# SNES_TST_Sheet3.net
KiCad netlist of a schematic drawn in Altium Designer
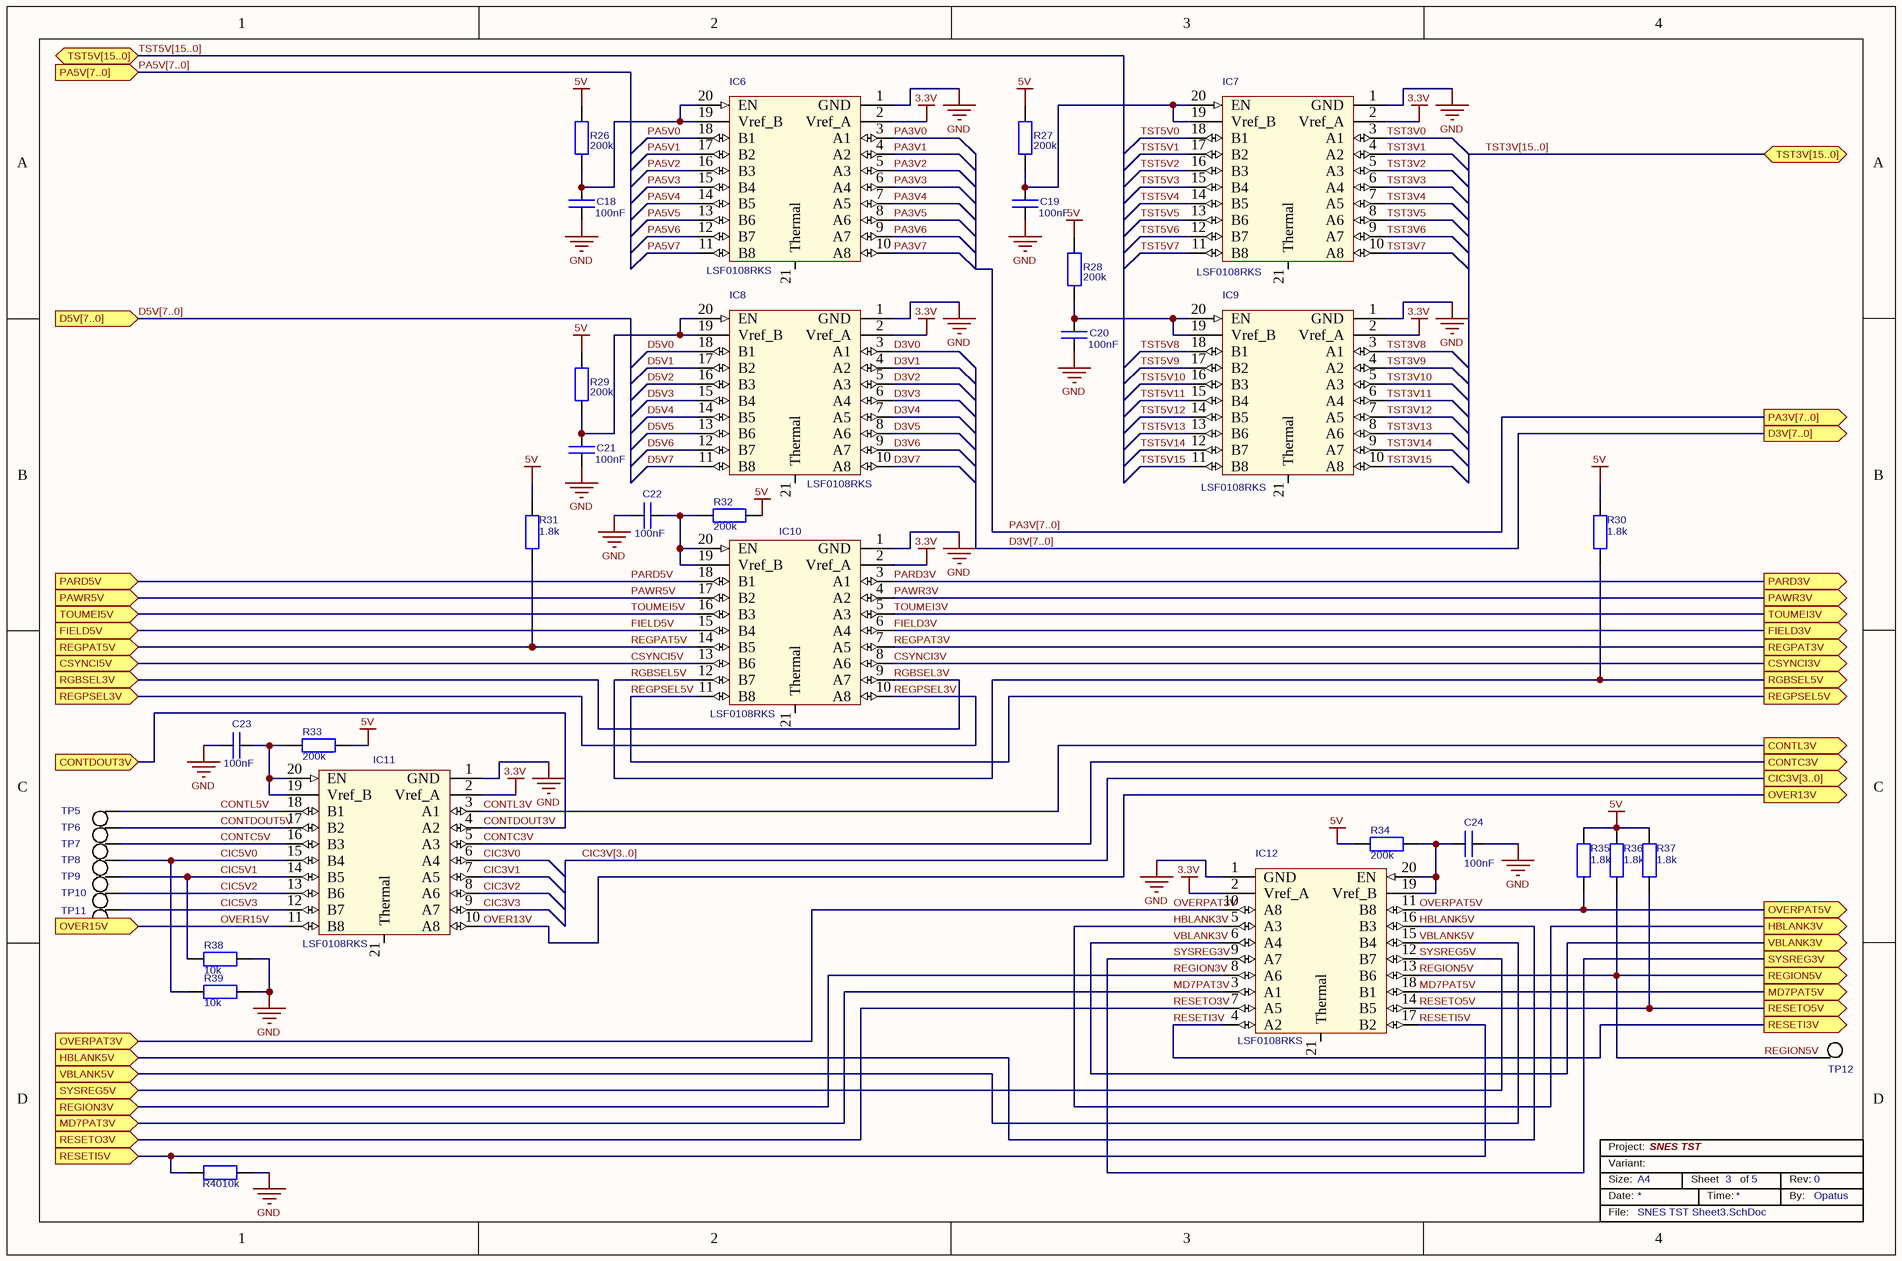
[diagram p0: SNES TST Sheet3.SchDoc]

(export (version "E")
  (design (tool "Eeschema 10.0.6"))
  (components
    (comp (ref "C18")
      (value "100nF")
      (footprint "Cap_0402_Chip")
      (fields
        (field (name "TOLERANCE") "±20%")
        (field (name "Comment") "Ceramic Capacitor 100nF 10V ±20% X7R 0402")
      )
      (libsource (lib "PCB") (part "Capacitor"))
    )
    (comp (ref "C19")
      (value "100nF")
      (footprint "Cap_0402_Chip")
      (fields
        (field (name "TOLERANCE") "±20%")
        (field (name "Comment") "Ceramic Capacitor 100nF 10V ±20% X7R 0402")
      )
      (libsource (lib "PCB") (part "Capacitor"))
    )
    (comp (ref "C20")
      (value "100nF")
      (footprint "Cap_0402_Chip")
      (fields
        (field (name "TOLERANCE") "±20%")
        (field (name "Comment") "Ceramic Capacitor 100nF 10V ±20% X7R 0402")
      )
      (libsource (lib "PCB") (part "Capacitor"))
    )
    (comp (ref "C21")
      (value "100nF")
      (footprint "Cap_0402_Chip")
      (fields
        (field (name "TOLERANCE") "±20%")
        (field (name "Comment") "Ceramic Capacitor 100nF 10V ±20% X7R 0402")
      )
      (libsource (lib "PCB") (part "Capacitor"))
    )
    (comp (ref "C22")
      (value "100nF")
      (footprint "Cap_0402_Chip")
      (fields
        (field (name "TOLERANCE") "±20%")
        (field (name "Comment") "Ceramic Capacitor 100nF 10V ±20% X7R 0402")
      )
      (libsource (lib "PCB") (part "Capacitor"))
    )
    (comp (ref "C23")
      (value "100nF")
      (footprint "Cap_0402_Chip")
      (fields
        (field (name "TOLERANCE") "±20%")
        (field (name "Comment") "Ceramic Capacitor 100nF 10V ±20% X7R 0402")
      )
      (libsource (lib "PCB") (part "Capacitor"))
    )
    (comp (ref "C24")
      (value "100nF")
      (footprint "Cap_0402_Chip")
      (fields
        (field (name "TOLERANCE") "±20%")
        (field (name "Comment") "Ceramic Capacitor 100nF 10V ±20% X7R 0402")
      )
      (libsource (lib "PCB") (part "Capacitor"))
    )
    (comp (ref "IC6")
      (value "LSF0108")
      (footprint "VQFN20")
      (description "8-bit level shifter")
      (fields (field (name "MANUFACTURER_PART_NUMBER") "LSF0108RKS"))
      (libsource (lib "PCB") (part "LSF0108DCUR"))
    )
    (comp (ref "IC7")
      (value "LSF0108")
      (footprint "VQFN20")
      (description "8-bit level shifter")
      (fields (field (name "MANUFACTURER_PART_NUMBER") "LSF0108RKS"))
      (libsource (lib "PCB") (part "LSF0108DCUR"))
    )
    (comp (ref "IC8")
      (value "LSF0108")
      (footprint "VQFN20")
      (description "8-bit level shifter")
      (fields (field (name "MANUFACTURER_PART_NUMBER") "LSF0108RKS"))
      (libsource (lib "PCB") (part "LSF0108DCUR"))
    )
    (comp (ref "IC9")
      (value "LSF0108")
      (footprint "VQFN20")
      (description "8-bit level shifter")
      (fields (field (name "MANUFACTURER_PART_NUMBER") "LSF0108RKS"))
      (libsource (lib "PCB") (part "LSF0108DCUR"))
    )
    (comp (ref "IC10")
      (value "LSF0108")
      (footprint "VQFN20")
      (description "8-bit level shifter")
      (fields (field (name "MANUFACTURER_PART_NUMBER") "LSF0108RKS"))
      (libsource (lib "PCB") (part "LSF0108DCUR"))
    )
    (comp (ref "IC11")
      (value "LSF0108")
      (footprint "VQFN20")
      (description "8-bit level shifter")
      (fields (field (name "MANUFACTURER_PART_NUMBER") "LSF0108RKS"))
      (libsource (lib "PCB") (part "LSF0108DCUR"))
    )
    (comp (ref "IC12")
      (value "LSF0108")
      (footprint "VQFN20")
      (description "8-bit level shifter")
      (fields (field (name "MANUFACTURER_PART_NUMBER") "LSF0108RKS"))
      (libsource (lib "") (part "LSF0108DCUR_1"))
    )
    (comp (ref "R26")
      (value "200k")
      (footprint "Res_0402_Chip")
      (fields (field (name "TOLERANCE") "±1%") (field (name "Comment") "Resistor 200k 0402 ±1%"))
      (libsource (lib "") (part "R_2"))
    )
    (comp (ref "R27")
      (value "200k")
      (footprint "Res_0402_Chip")
      (fields (field (name "TOLERANCE") "±1%") (field (name "Comment") "Resistor 200k 0402 ±1%"))
      (libsource (lib "") (part "R_2"))
    )
    (comp (ref "R28")
      (value "200k")
      (footprint "Res_0402_Chip")
      (fields (field (name "TOLERANCE") "±1%") (field (name "Comment") "Resistor 200k 0402 ±1%"))
      (libsource (lib "") (part "R_2"))
    )
    (comp (ref "R29")
      (value "200k")
      (footprint "Res_0402_Chip")
      (fields (field (name "TOLERANCE") "±1%") (field (name "Comment") "Resistor 200k 0402 ±1%"))
      (libsource (lib "") (part "R_2"))
    )
    (comp (ref "R30")
      (value "1.8k")
      (footprint "Res_0402_Chip")
      (fields (field (name "TOLERANCE") "±1%") (field (name "Comment") "Resistor 1.8k 0402 ±1%"))
      (libsource (lib "PCB") (part "R"))
    )
    (comp (ref "R31")
      (value "1.8k")
      (footprint "Res_0402_Chip")
      (fields (field (name "TOLERANCE") "±1%") (field (name "Comment") "Resistor 1.8k 0402 ±1%"))
      (libsource (lib "PCB") (part "R"))
    )
    (comp (ref "R32")
      (value "200k")
      (footprint "Res_0402_Chip")
      (fields (field (name "TOLERANCE") "±1%") (field (name "Comment") "Resistor 200k 0402 ±1%"))
      (libsource (lib "") (part "R_1"))
    )
    (comp (ref "R33")
      (value "200k")
      (footprint "Res_0402_Chip")
      (fields (field (name "TOLERANCE") "±1%") (field (name "Comment") "Resistor 200k 0402 ±1%"))
      (libsource (lib "") (part "R_1"))
    )
    (comp (ref "R34")
      (value "200k")
      (footprint "Res_0402_Chip")
      (fields (field (name "TOLERANCE") "±1%") (field (name "Comment") "Resistor 200k 0402 ±1%"))
      (libsource (lib "") (part "R_1"))
    )
    (comp (ref "R35")
      (value "1.8k")
      (footprint "Res_0402_Chip")
      (fields (field (name "TOLERANCE") "±1%") (field (name "Comment") "Resistor 1.8k 0402 ±1%"))
      (libsource (lib "PCB") (part "R"))
    )
    (comp (ref "R36")
      (value "1.8k")
      (footprint "Res_0402_Chip")
      (fields (field (name "TOLERANCE") "±1%") (field (name "Comment") "Resistor 1.8k 0402 ±1%"))
      (libsource (lib "PCB") (part "R"))
    )
    (comp (ref "R37")
      (value "1.8k")
      (footprint "Res_0402_Chip")
      (fields (field (name "TOLERANCE") "±1%") (field (name "Comment") "Resistor 1.8k 0402 ±1%"))
      (libsource (lib "PCB") (part "R"))
    )
    (comp (ref "R38")
      (value "10k")
      (footprint "Res_0402_Chip")
      (fields (field (name "TOLERANCE") "±1%") (field (name "Comment") "Resistor 10k 0402 ±1%"))
      (libsource (lib "") (part "R_1"))
    )
    (comp (ref "R39")
      (value "10k")
      (footprint "Res_0402_Chip")
      (fields (field (name "TOLERANCE") "±1%") (field (name "Comment") "Resistor 10k 0402 ±1%"))
      (libsource (lib "") (part "R_1"))
    )
    (comp (ref "R40")
      (value "10k")
      (footprint "Res_0402_Chip")
      (fields (field (name "TOLERANCE") "±1%") (field (name "Comment") "Resistor 10k 0402 ±1%"))
      (libsource (lib "") (part "R_3"))
    )
    (comp (ref "TP5")
      (value "Pin Connector")
      (footprint "Pin Connector Small")
      (libsource (lib "PCB") (part "Pin Connector"))
    )
    (comp (ref "TP6")
      (value "Pin Connector")
      (footprint "Pin Connector Small")
      (libsource (lib "PCB") (part "Pin Connector"))
    )
    (comp (ref "TP7")
      (value "Pin Connector")
      (footprint "Pin Connector Small")
      (libsource (lib "PCB") (part "Pin Connector"))
    )
    (comp (ref "TP8")
      (value "Pin Connector")
      (footprint "Pin Connector Small")
      (libsource (lib "PCB") (part "Pin Connector"))
    )
    (comp (ref "TP9")
      (value "Pin Connector")
      (footprint "Pin Connector Small")
      (libsource (lib "PCB") (part "Pin Connector"))
    )
    (comp (ref "TP10")
      (value "Pin Connector")
      (footprint "Pin Connector Small")
      (libsource (lib "PCB") (part "Pin Connector"))
    )
    (comp (ref "TP11")
      (value "Pin Connector")
      (footprint "Pin Connector Small")
      (libsource (lib "PCB") (part "Pin Connector"))
    )
    (comp (ref "TP12")
      (value "Pin Connector")
      (footprint "Pin Connector Small")
      (libsource (lib "PCB") (part "Pin Connector"))
    )
  )
  (nets
    (net (code "1") (name "/CIC3V0") (class "Default")
      (node (ref "IC11") (pin "6") (pinfunction "A4_6") (pintype "bidirectional"))
    )
    (net (code "2") (name "/CIC3V1") (class "Default")
      (node (ref "IC11") (pin "7") (pinfunction "A5_7") (pintype "bidirectional"))
    )
    (net (code "3") (name "/CIC3V2") (class "Default")
      (node (ref "IC11") (pin "8") (pinfunction "A6_8") (pintype "bidirectional"))
    )
    (net (code "4") (name "/CIC3V3") (class "Default")
      (node (ref "IC11") (pin "9") (pinfunction "A7_9") (pintype "bidirectional"))
    )
    (net (code "6") (name "/CIC5V0") (class "Default")
      (node (ref "IC11") (pin "15") (pinfunction "B4_15") (pintype "bidirectional"))
      (node (ref "R39") (pin "2") (pintype "passive"))
      (node (ref "TP8") (pin "1") (pinfunction "0_1") (pintype "passive"))
    )
    (net (code "7") (name "/CIC5V1") (class "Default")
      (node (ref "IC11") (pin "14") (pinfunction "B5_14") (pintype "bidirectional"))
      (node (ref "R38") (pin "2") (pintype "passive"))
      (node (ref "TP9") (pin "1") (pinfunction "0_1") (pintype "passive"))
    )
    (net (code "8") (name "/CIC5V2") (class "Default")
      (node (ref "IC11") (pin "13") (pinfunction "B6_13") (pintype "bidirectional"))
      (node (ref "TP10") (pin "1") (pinfunction "0_1") (pintype "passive"))
    )
    (net (code "9") (name "/CIC5V3") (class "Default")
      (node (ref "IC11") (pin "12") (pinfunction "B7_12") (pintype "bidirectional"))
      (node (ref "TP11") (pin "1") (pinfunction "0_1") (pintype "passive"))
    )
    (net (code "10") (name "/CONTC3V") (class "Default")
      (node (ref "IC11") (pin "5") (pinfunction "A3_5") (pintype "bidirectional"))
    )
    (net (code "11") (name "/CONTC5V") (class "Default")
      (node (ref "IC11") (pin "16") (pinfunction "B3_16") (pintype "bidirectional"))
      (node (ref "TP7") (pin "1") (pinfunction "0_1") (pintype "passive"))
    )
    (net (code "12") (name "/CONTDOUT3V") (class "Default")
      (node (ref "IC11") (pin "4") (pinfunction "A2_4") (pintype "bidirectional"))
    )
    (net (code "13") (name "/CONTDOUT5V") (class "Default")
      (node (ref "IC11") (pin "17") (pinfunction "B2_17") (pintype "bidirectional"))
      (node (ref "TP6") (pin "1") (pinfunction "0_1") (pintype "passive"))
    )
    (net (code "14") (name "/CONTL3V") (class "Default")
      (node (ref "IC11") (pin "3") (pinfunction "A1_3") (pintype "bidirectional"))
    )
    (net (code "15") (name "/CONTL5V") (class "Default")
      (node (ref "IC11") (pin "18") (pinfunction "B1_18") (pintype "bidirectional"))
      (node (ref "TP5") (pin "1") (pinfunction "0_1") (pintype "passive"))
    )
    (net (code "16") (name "/CSYNCI3V") (class "Default")
      (node (ref "IC10") (pin "8") (pinfunction "A6_8") (pintype "bidirectional"))
    )
    (net (code "17") (name "/CSYNCI5V") (class "Default")
      (node (ref "IC10") (pin "13") (pinfunction "B6_13") (pintype "bidirectional"))
    )
    (net (code "18") (name "/D3V0") (class "Default")
      (node (ref "IC8") (pin "3") (pinfunction "A1_3") (pintype "bidirectional"))
    )
    (net (code "19") (name "/D3V1") (class "Default")
      (node (ref "IC8") (pin "4") (pinfunction "A2_4") (pintype "bidirectional"))
    )
    (net (code "20") (name "/D3V2") (class "Default")
      (node (ref "IC8") (pin "5") (pinfunction "A3_5") (pintype "bidirectional"))
    )
    (net (code "21") (name "/D3V3") (class "Default")
      (node (ref "IC8") (pin "6") (pinfunction "A4_6") (pintype "bidirectional"))
    )
    (net (code "22") (name "/D3V4") (class "Default")
      (node (ref "IC8") (pin "7") (pinfunction "A5_7") (pintype "bidirectional"))
    )
    (net (code "23") (name "/D3V5") (class "Default")
      (node (ref "IC8") (pin "8") (pinfunction "A6_8") (pintype "bidirectional"))
    )
    (net (code "24") (name "/D3V6") (class "Default")
      (node (ref "IC8") (pin "9") (pinfunction "A7_9") (pintype "bidirectional"))
    )
    (net (code "25") (name "/D3V7") (class "Default")
      (node (ref "IC8") (pin "10") (pinfunction "A8_10") (pintype "bidirectional"))
    )
    (net (code "27") (name "/D5V0") (class "Default")
      (node (ref "IC8") (pin "18") (pinfunction "B1_18") (pintype "bidirectional"))
    )
    (net (code "28") (name "/D5V1") (class "Default")
      (node (ref "IC8") (pin "17") (pinfunction "B2_17") (pintype "bidirectional"))
    )
    (net (code "29") (name "/D5V2") (class "Default")
      (node (ref "IC8") (pin "16") (pinfunction "B3_16") (pintype "bidirectional"))
    )
    (net (code "30") (name "/D5V3") (class "Default")
      (node (ref "IC8") (pin "15") (pinfunction "B4_15") (pintype "bidirectional"))
    )
    (net (code "31") (name "/D5V4") (class "Default")
      (node (ref "IC8") (pin "14") (pinfunction "B5_14") (pintype "bidirectional"))
    )
    (net (code "32") (name "/D5V5") (class "Default")
      (node (ref "IC8") (pin "13") (pinfunction "B6_13") (pintype "bidirectional"))
    )
    (net (code "33") (name "/D5V6") (class "Default")
      (node (ref "IC8") (pin "12") (pinfunction "B7_12") (pintype "bidirectional"))
    )
    (net (code "34") (name "/D5V7") (class "Default")
      (node (ref "IC8") (pin "11") (pinfunction "B8_11") (pintype "bidirectional"))
    )
    (net (code "36") (name "/FIELD3V") (class "Default")
      (node (ref "IC10") (pin "6") (pinfunction "A4_6") (pintype "bidirectional"))
    )
    (net (code "37") (name "/FIELD5V") (class "Default")
      (node (ref "IC10") (pin "15") (pinfunction "B4_15") (pintype "bidirectional"))
    )
    (net (code "38") (name "/HBLANK3V") (class "Default")
      (node (ref "IC12") (pin "5") (pinfunction "A3_5") (pintype "bidirectional"))
    )
    (net (code "39") (name "/HBLANK5V") (class "Default")
      (node (ref "IC12") (pin "16") (pinfunction "B3_16") (pintype "bidirectional"))
    )
    (net (code "40") (name "/MD7PAT3V") (class "Default")
      (node (ref "IC12") (pin "3") (pinfunction "A1_3") (pintype "bidirectional"))
    )
    (net (code "41") (name "/MD7PAT5V") (class "Default")
      (node (ref "IC12") (pin "18") (pinfunction "B1_18") (pintype "bidirectional"))
    )
    (net (code "42") (name "/OVER13V") (class "Default")
      (node (ref "IC11") (pin "10") (pinfunction "A8_10") (pintype "bidirectional"))
    )
    (net (code "43") (name "/OVER15V") (class "Default")
      (node (ref "IC11") (pin "11") (pinfunction "B8_11") (pintype "bidirectional"))
    )
    (net (code "44") (name "/OVERPAT3V") (class "Default")
      (node (ref "IC12") (pin "10") (pinfunction "A8_10") (pintype "bidirectional"))
    )
    (net (code "45") (name "/OVERPAT5V") (class "Default")
      (node (ref "IC12") (pin "11") (pinfunction "B8_11") (pintype "bidirectional"))
      (node (ref "R35") (pin "2") (pintype "passive"))
    )
    (net (code "46") (name "/PA3V0") (class "Default")
      (node (ref "IC6") (pin "3") (pinfunction "A1_3") (pintype "bidirectional"))
    )
    (net (code "47") (name "/PA3V1") (class "Default")
      (node (ref "IC6") (pin "4") (pinfunction "A2_4") (pintype "bidirectional"))
    )
    (net (code "48") (name "/PA3V2") (class "Default")
      (node (ref "IC6") (pin "5") (pinfunction "A3_5") (pintype "bidirectional"))
    )
    (net (code "49") (name "/PA3V3") (class "Default")
      (node (ref "IC6") (pin "6") (pinfunction "A4_6") (pintype "bidirectional"))
    )
    (net (code "50") (name "/PA3V4") (class "Default")
      (node (ref "IC6") (pin "7") (pinfunction "A5_7") (pintype "bidirectional"))
    )
    (net (code "51") (name "/PA3V5") (class "Default")
      (node (ref "IC6") (pin "8") (pinfunction "A6_8") (pintype "bidirectional"))
    )
    (net (code "52") (name "/PA3V6") (class "Default")
      (node (ref "IC6") (pin "9") (pinfunction "A7_9") (pintype "bidirectional"))
    )
    (net (code "53") (name "/PA3V7") (class "Default")
      (node (ref "IC6") (pin "10") (pinfunction "A8_10") (pintype "bidirectional"))
    )
    (net (code "55") (name "/PA5V0") (class "Default")
      (node (ref "IC6") (pin "18") (pinfunction "B1_18") (pintype "bidirectional"))
    )
    (net (code "56") (name "/PA5V1") (class "Default")
      (node (ref "IC6") (pin "17") (pinfunction "B2_17") (pintype "bidirectional"))
    )
    (net (code "57") (name "/PA5V2") (class "Default")
      (node (ref "IC6") (pin "16") (pinfunction "B3_16") (pintype "bidirectional"))
    )
    (net (code "58") (name "/PA5V3") (class "Default")
      (node (ref "IC6") (pin "15") (pinfunction "B4_15") (pintype "bidirectional"))
    )
    (net (code "59") (name "/PA5V4") (class "Default")
      (node (ref "IC6") (pin "14") (pinfunction "B5_14") (pintype "bidirectional"))
    )
    (net (code "60") (name "/PA5V5") (class "Default")
      (node (ref "IC6") (pin "13") (pinfunction "B6_13") (pintype "bidirectional"))
    )
    (net (code "61") (name "/PA5V6") (class "Default")
      (node (ref "IC6") (pin "12") (pinfunction "B7_12") (pintype "bidirectional"))
    )
    (net (code "62") (name "/PA5V7") (class "Default")
      (node (ref "IC6") (pin "11") (pinfunction "B8_11") (pintype "bidirectional"))
    )
    (net (code "64") (name "/PARD3V") (class "Default")
      (node (ref "IC10") (pin "3") (pinfunction "A1_3") (pintype "bidirectional"))
    )
    (net (code "65") (name "/PARD5V") (class "Default")
      (node (ref "IC10") (pin "18") (pinfunction "B1_18") (pintype "bidirectional"))
    )
    (net (code "66") (name "/PAWR3V") (class "Default")
      (node (ref "IC10") (pin "4") (pinfunction "A2_4") (pintype "bidirectional"))
    )
    (net (code "67") (name "/PAWR5V") (class "Default")
      (node (ref "IC10") (pin "17") (pinfunction "B2_17") (pintype "bidirectional"))
    )
    (net (code "68") (name "/REGION3V") (class "Default")
      (node (ref "IC12") (pin "8") (pinfunction "A6_8") (pintype "bidirectional"))
    )
    (net (code "69") (name "/REGION5V") (class "Default")
      (node (ref "IC12") (pin "13") (pinfunction "B6_13") (pintype "bidirectional"))
      (node (ref "R36") (pin "2") (pintype "passive"))
      (node (ref "TP12") (pin "1") (pinfunction "0_1") (pintype "passive"))
    )
    (net (code "70") (name "/REGPAT3V") (class "Default")
      (node (ref "IC10") (pin "7") (pinfunction "A5_7") (pintype "bidirectional"))
    )
    (net (code "71") (name "/REGPAT5V") (class "Default")
      (node (ref "IC10") (pin "14") (pinfunction "B5_14") (pintype "bidirectional"))
      (node (ref "R31") (pin "2") (pintype "passive"))
    )
    (net (code "72") (name "/REGPSEL3V") (class "Default")
      (node (ref "IC10") (pin "10") (pinfunction "A8_10") (pintype "bidirectional"))
    )
    (net (code "73") (name "/REGPSEL5V") (class "Default")
      (node (ref "IC10") (pin "11") (pinfunction "B8_11") (pintype "bidirectional"))
    )
    (net (code "74") (name "/RESETI3V") (class "Default")
      (node (ref "IC12") (pin "4") (pinfunction "A2_4") (pintype "bidirectional"))
    )
    (net (code "75") (name "/RESETI5V") (class "Default")
      (node (ref "IC12") (pin "17") (pinfunction "B2_17") (pintype "bidirectional"))
      (node (ref "R40") (pin "1") (pintype "passive"))
    )
    (net (code "76") (name "/RESETO3V") (class "Default")
      (node (ref "IC12") (pin "7") (pinfunction "A5_7") (pintype "bidirectional"))
    )
    (net (code "77") (name "/RESETO5V") (class "Default")
      (node (ref "IC12") (pin "14") (pinfunction "B5_14") (pintype "bidirectional"))
      (node (ref "R37") (pin "2") (pintype "passive"))
    )
    (net (code "78") (name "/RGBSEL3V") (class "Default")
      (node (ref "IC10") (pin "9") (pinfunction "A7_9") (pintype "bidirectional"))
    )
    (net (code "79") (name "/RGBSEL5V") (class "Default")
      (node (ref "IC10") (pin "12") (pinfunction "B7_12") (pintype "bidirectional"))
      (node (ref "R30") (pin "2") (pintype "passive"))
    )
    (net (code "80") (name "/SYSREG3V") (class "Default")
      (node (ref "IC12") (pin "9") (pinfunction "A7_9") (pintype "bidirectional"))
    )
    (net (code "81") (name "/SYSREG5V") (class "Default")
      (node (ref "IC12") (pin "12") (pinfunction "B7_12") (pintype "bidirectional"))
    )
    (net (code "82") (name "/TOUMEI3V") (class "Default")
      (node (ref "IC10") (pin "5") (pinfunction "A3_5") (pintype "bidirectional"))
    )
    (net (code "83") (name "/TOUMEI5V") (class "Default")
      (node (ref "IC10") (pin "16") (pinfunction "B3_16") (pintype "bidirectional"))
    )
    (net (code "84") (name "/TST3V0") (class "Default")
      (node (ref "IC7") (pin "3") (pinfunction "A1_3") (pintype "bidirectional"))
    )
    (net (code "85") (name "/TST3V1") (class "Default")
      (node (ref "IC7") (pin "4") (pinfunction "A2_4") (pintype "bidirectional"))
    )
    (net (code "86") (name "/TST3V2") (class "Default")
      (node (ref "IC7") (pin "5") (pinfunction "A3_5") (pintype "bidirectional"))
    )
    (net (code "87") (name "/TST3V3") (class "Default")
      (node (ref "IC7") (pin "6") (pinfunction "A4_6") (pintype "bidirectional"))
    )
    (net (code "88") (name "/TST3V4") (class "Default")
      (node (ref "IC7") (pin "7") (pinfunction "A5_7") (pintype "bidirectional"))
    )
    (net (code "89") (name "/TST3V5") (class "Default")
      (node (ref "IC7") (pin "8") (pinfunction "A6_8") (pintype "bidirectional"))
    )
    (net (code "90") (name "/TST3V6") (class "Default")
      (node (ref "IC7") (pin "9") (pinfunction "A7_9") (pintype "bidirectional"))
    )
    (net (code "91") (name "/TST3V7") (class "Default")
      (node (ref "IC7") (pin "10") (pinfunction "A8_10") (pintype "bidirectional"))
    )
    (net (code "92") (name "/TST3V8") (class "Default")
      (node (ref "IC9") (pin "3") (pinfunction "A1_3") (pintype "bidirectional"))
    )
    (net (code "93") (name "/TST3V9") (class "Default")
      (node (ref "IC9") (pin "4") (pinfunction "A2_4") (pintype "bidirectional"))
    )
    (net (code "94") (name "/TST3V10") (class "Default")
      (node (ref "IC9") (pin "5") (pinfunction "A3_5") (pintype "bidirectional"))
    )
    (net (code "95") (name "/TST3V11") (class "Default")
      (node (ref "IC9") (pin "6") (pinfunction "A4_6") (pintype "bidirectional"))
    )
    (net (code "96") (name "/TST3V12") (class "Default")
      (node (ref "IC9") (pin "7") (pinfunction "A5_7") (pintype "bidirectional"))
    )
    (net (code "97") (name "/TST3V13") (class "Default")
      (node (ref "IC9") (pin "8") (pinfunction "A6_8") (pintype "bidirectional"))
    )
    (net (code "98") (name "/TST3V14") (class "Default")
      (node (ref "IC9") (pin "9") (pinfunction "A7_9") (pintype "bidirectional"))
    )
    (net (code "99") (name "/TST3V15") (class "Default")
      (node (ref "IC9") (pin "10") (pinfunction "A8_10") (pintype "bidirectional"))
    )
    (net (code "101") (name "/TST5V0") (class "Default")
      (node (ref "IC7") (pin "18") (pinfunction "B1_18") (pintype "bidirectional"))
    )
    (net (code "102") (name "/TST5V1") (class "Default")
      (node (ref "IC7") (pin "17") (pinfunction "B2_17") (pintype "bidirectional"))
    )
    (net (code "103") (name "/TST5V2") (class "Default")
      (node (ref "IC7") (pin "16") (pinfunction "B3_16") (pintype "bidirectional"))
    )
    (net (code "104") (name "/TST5V3") (class "Default")
      (node (ref "IC7") (pin "15") (pinfunction "B4_15") (pintype "bidirectional"))
    )
    (net (code "105") (name "/TST5V4") (class "Default")
      (node (ref "IC7") (pin "14") (pinfunction "B5_14") (pintype "bidirectional"))
    )
    (net (code "106") (name "/TST5V5") (class "Default")
      (node (ref "IC7") (pin "13") (pinfunction "B6_13") (pintype "bidirectional"))
    )
    (net (code "107") (name "/TST5V6") (class "Default")
      (node (ref "IC7") (pin "12") (pinfunction "B7_12") (pintype "bidirectional"))
    )
    (net (code "108") (name "/TST5V7") (class "Default")
      (node (ref "IC7") (pin "11") (pinfunction "B8_11") (pintype "bidirectional"))
    )
    (net (code "109") (name "/TST5V8") (class "Default")
      (node (ref "IC9") (pin "18") (pinfunction "B1_18") (pintype "bidirectional"))
    )
    (net (code "110") (name "/TST5V9") (class "Default")
      (node (ref "IC9") (pin "17") (pinfunction "B2_17") (pintype "bidirectional"))
    )
    (net (code "111") (name "/TST5V10") (class "Default")
      (node (ref "IC9") (pin "16") (pinfunction "B3_16") (pintype "bidirectional"))
    )
    (net (code "112") (name "/TST5V11") (class "Default")
      (node (ref "IC9") (pin "15") (pinfunction "B4_15") (pintype "bidirectional"))
    )
    (net (code "113") (name "/TST5V12") (class "Default")
      (node (ref "IC9") (pin "14") (pinfunction "B5_14") (pintype "bidirectional"))
    )
    (net (code "114") (name "/TST5V13") (class "Default")
      (node (ref "IC9") (pin "13") (pinfunction "B6_13") (pintype "bidirectional"))
    )
    (net (code "115") (name "/TST5V14") (class "Default")
      (node (ref "IC9") (pin "12") (pinfunction "B7_12") (pintype "bidirectional"))
    )
    (net (code "116") (name "/TST5V15") (class "Default")
      (node (ref "IC9") (pin "11") (pinfunction "B8_11") (pintype "bidirectional"))
    )
    (net (code "118") (name "/VBLANK3V") (class "Default")
      (node (ref "IC12") (pin "6") (pinfunction "A4_6") (pintype "bidirectional"))
    )
    (net (code "119") (name "/VBLANK5V") (class "Default")
      (node (ref "IC12") (pin "15") (pinfunction "B4_15") (pintype "bidirectional"))
    )
    (net (code "120") (name "3.3V") (class "Default")
      (node (ref "IC10") (pin "2") (pinfunction "Vref_A_2") (pintype "power_in"))
      (node (ref "IC11") (pin "2") (pinfunction "Vref_A_2") (pintype "power_in"))
      (node (ref "IC12") (pin "2") (pinfunction "Vref_A_2") (pintype "power_in"))
      (node (ref "IC6") (pin "2") (pinfunction "Vref_A_2") (pintype "power_in"))
      (node (ref "IC7") (pin "2") (pinfunction "Vref_A_2") (pintype "power_in"))
      (node (ref "IC8") (pin "2") (pinfunction "Vref_A_2") (pintype "power_in"))
      (node (ref "IC9") (pin "2") (pinfunction "Vref_A_2") (pintype "power_in"))
    )
    (net (code "121") (name "5V") (class "Default")
      (node (ref "R26") (pin "2") (pintype "passive"))
      (node (ref "R27") (pin "2") (pintype "passive"))
      (node (ref "R28") (pin "2") (pintype "passive"))
      (node (ref "R29") (pin "2") (pintype "passive"))
      (node (ref "R30") (pin "1") (pintype "passive"))
      (node (ref "R31") (pin "1") (pintype "passive"))
      (node (ref "R32") (pin "1") (pintype "passive"))
      (node (ref "R33") (pin "1") (pintype "passive"))
      (node (ref "R34") (pin "2") (pintype "passive"))
      (node (ref "R35") (pin "1") (pintype "passive"))
      (node (ref "R36") (pin "1") (pintype "passive"))
      (node (ref "R37") (pin "1") (pintype "passive"))
    )
    (net (code "122") (name "GND") (class "Default")
      (node (ref "C18") (pin "2") (pintype "passive"))
      (node (ref "C19") (pin "2") (pintype "passive"))
      (node (ref "C20") (pin "2") (pintype "passive"))
      (node (ref "C21") (pin "2") (pintype "passive"))
      (node (ref "C22") (pin "1") (pintype "passive"))
      (node (ref "C23") (pin "1") (pintype "passive"))
      (node (ref "C24") (pin "2") (pintype "passive"))
      (node (ref "IC10") (pin "1") (pinfunction "GND_1") (pintype "power_in"))
      (node (ref "IC11") (pin "1") (pinfunction "GND_1") (pintype "power_in"))
      (node (ref "IC12") (pin "1") (pinfunction "GND_1") (pintype "power_in"))
      (node (ref "IC6") (pin "1") (pinfunction "GND_1") (pintype "power_in"))
      (node (ref "IC7") (pin "1") (pinfunction "GND_1") (pintype "power_in"))
      (node (ref "IC8") (pin "1") (pinfunction "GND_1") (pintype "power_in"))
      (node (ref "IC9") (pin "1") (pinfunction "GND_1") (pintype "power_in"))
      (node (ref "R38") (pin "1") (pintype "passive"))
      (node (ref "R39") (pin "1") (pintype "passive"))
      (node (ref "R40") (pin "2") (pintype "passive"))
    )
    (net (code "123") (name "Net-(IC6-EN)") (class "Default")
      (node (ref "C18") (pin "1") (pintype "passive"))
      (node (ref "IC6") (pin "19") (pinfunction "Vref_B_19") (pintype "power_in"))
      (node (ref "IC6") (pin "20") (pinfunction "EN_20") (pintype "input"))
      (node (ref "R26") (pin "1") (pintype "passive"))
    )
    (net (code "124") (name "Net-(IC7-EN)") (class "Default")
      (node (ref "C19") (pin "1") (pintype "passive"))
      (node (ref "IC7") (pin "19") (pinfunction "Vref_B_19") (pintype "power_in"))
      (node (ref "IC7") (pin "20") (pinfunction "EN_20") (pintype "input"))
      (node (ref "R27") (pin "1") (pintype "passive"))
    )
    (net (code "125") (name "Net-(IC8-EN)") (class "Default")
      (node (ref "C21") (pin "1") (pintype "passive"))
      (node (ref "IC8") (pin "19") (pinfunction "Vref_B_19") (pintype "power_in"))
      (node (ref "IC8") (pin "20") (pinfunction "EN_20") (pintype "input"))
      (node (ref "R29") (pin "1") (pintype "passive"))
    )
    (net (code "126") (name "Net-(IC9-EN)") (class "Default")
      (node (ref "C20") (pin "1") (pintype "passive"))
      (node (ref "IC9") (pin "19") (pinfunction "Vref_B_19") (pintype "power_in"))
      (node (ref "IC9") (pin "20") (pinfunction "EN_20") (pintype "input"))
      (node (ref "R28") (pin "1") (pintype "passive"))
    )
    (net (code "127") (name "Net-(IC10-EN)") (class "Default")
      (node (ref "C22") (pin "2") (pintype "passive"))
      (node (ref "IC10") (pin "19") (pinfunction "Vref_B_19") (pintype "power_in"))
      (node (ref "IC10") (pin "20") (pinfunction "EN_20") (pintype "input"))
      (node (ref "R32") (pin "2") (pintype "passive"))
    )
    (net (code "128") (name "Net-(IC11-EN)") (class "Default")
      (node (ref "C23") (pin "2") (pintype "passive"))
      (node (ref "IC11") (pin "19") (pinfunction "Vref_B_19") (pintype "power_in"))
      (node (ref "IC11") (pin "20") (pinfunction "EN_20") (pintype "input"))
      (node (ref "R33") (pin "2") (pintype "passive"))
    )
    (net (code "129") (name "Net-(IC12-EN)") (class "Default")
      (node (ref "C24") (pin "1") (pintype "passive"))
      (node (ref "IC12") (pin "19") (pinfunction "Vref_B_19") (pintype "power_in"))
      (node (ref "IC12") (pin "20") (pinfunction "EN_20") (pintype "input"))
      (node (ref "R34") (pin "1") (pintype "passive"))
    )
    (net (code "130") (name "unconnected-(IC6-Thermal-Pad21)") (class "Default")
      (node (ref "IC6") (pin "21") (pinfunction "Thermal_21") (pintype "passive"))
    )
    (net (code "131") (name "unconnected-(IC7-Thermal-Pad21)") (class "Default")
      (node (ref "IC7") (pin "21") (pinfunction "Thermal_21") (pintype "passive"))
    )
    (net (code "132") (name "unconnected-(IC8-Thermal-Pad21)") (class "Default")
      (node (ref "IC8") (pin "21") (pinfunction "Thermal_21") (pintype "passive"))
    )
    (net (code "133") (name "unconnected-(IC9-Thermal-Pad21)") (class "Default")
      (node (ref "IC9") (pin "21") (pinfunction "Thermal_21") (pintype "passive"))
    )
    (net (code "134") (name "unconnected-(IC10-Thermal-Pad21)") (class "Default")
      (node (ref "IC10") (pin "21") (pinfunction "Thermal_21") (pintype "passive"))
    )
    (net (code "135") (name "unconnected-(IC11-Thermal-Pad21)") (class "Default")
      (node (ref "IC11") (pin "21") (pinfunction "Thermal_21") (pintype "passive"))
    )
    (net (code "136") (name "unconnected-(IC12-Thermal-Pad21)") (class "Default")
      (node (ref "IC12") (pin "21") (pinfunction "Thermal_21") (pintype "passive"))
    )
  )
)
